# 6N137.net
KiCad netlist of a schematic drawn in EAGLE
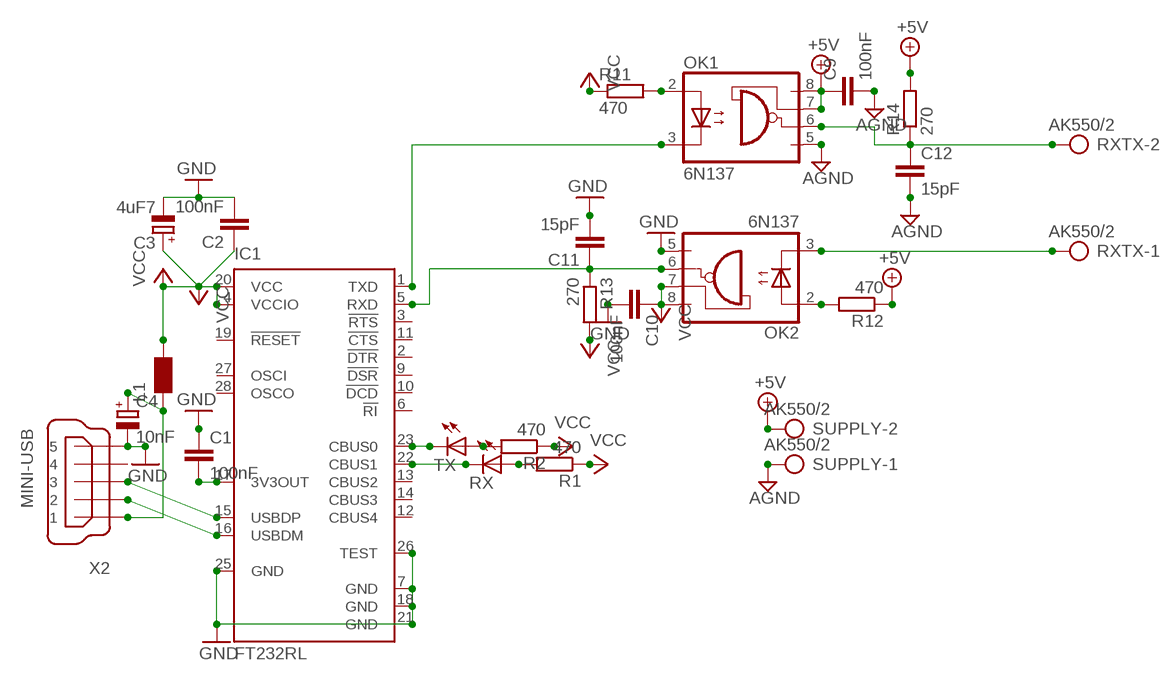
[diagram p0: schematic, sheet 1]

(export (version "E")
  (design (tool "Eeschema 10.0.6"))
  (components
    (comp (ref "C1")
      (value "100nF")
      (footprint "eagle-import:C1206K")
      (libsource (lib "eagle-import") (part "C-EUC1206K"))
    )
    (comp (ref "C2")
      (value "100nF")
      (footprint "eagle-import:C1206K")
      (libsource (lib "eagle-import") (part "C-EUC1206K"))
    )
    (comp (ref "C3")
      (value "4uF7")
      (footprint "eagle-import:153CLV-0605")
      (libsource (lib "eagle-import") (part "CPOL-EU153CLV-0605"))
    )
    (comp (ref "C4")
      (value "10nF")
      (footprint "eagle-import:153CLV-0405")
      (libsource (lib "eagle-import") (part "CPOL-EU153CLV-0405"))
    )
    (comp (ref "C9")
      (value "100nF")
      (footprint "eagle-import:C1206")
      (libsource (lib "eagle-import") (part "C-EUC1206"))
    )
    (comp (ref "C10")
      (value "100nF")
      (footprint "eagle-import:C1206")
      (libsource (lib "eagle-import") (part "C-EUC1206"))
    )
    (comp (ref "C11")
      (value "15pF")
      (footprint "eagle-import:C1206")
      (libsource (lib "eagle-import") (part "C-EUC1206"))
    )
    (comp (ref "C12")
      (value "15pF")
      (footprint "eagle-import:C1206")
      (libsource (lib "eagle-import") (part "C-EUC1206"))
    )
    (comp (ref "IC1")
      (value "FT232RL")
      (footprint "eagle-import:SSOP28")
      (libsource (lib "eagle-import") (part "FT232RL"))
    )
    (comp (ref "L1")
      (value "WE-CBF_1206")
      (footprint "eagle-import:1206")
      (libsource (lib "eagle-import") (part "WE-CBF_1206"))
    )
    (comp (ref "OK1")
      (value "6N137")
      (footprint "eagle-import:DIL08")
      (libsource (lib "eagle-import") (part "6N137"))
    )
    (comp (ref "OK2")
      (value "6N137")
      (footprint "eagle-import:DIL08")
      (libsource (lib "eagle-import") (part "6N137"))
    )
    (comp (ref "R1")
      (value "470")
      (footprint "eagle-import:M1206")
      (libsource (lib "eagle-import") (part "resistor_R-EU_M1206"))
    )
    (comp (ref "R2")
      (value "470")
      (footprint "eagle-import:M1206")
      (libsource (lib "eagle-import") (part "resistor_R-EU_M1206"))
    )
    (comp (ref "R11")
      (value "470")
      (footprint "eagle-import:R1206")
      (libsource (lib "eagle-import") (part "R-EU_R1206"))
    )
    (comp (ref "R12")
      (value "470")
      (footprint "eagle-import:R1206")
      (libsource (lib "eagle-import") (part "R-EU_R1206"))
    )
    (comp (ref "R13")
      (value "270")
      (footprint "eagle-import:R1206")
      (libsource (lib "eagle-import") (part "R-EU_R1206"))
    )
    (comp (ref "R14")
      (value "270")
      (footprint "eagle-import:R1206")
      (libsource (lib "eagle-import") (part "R-EU_R1206"))
    )
    (comp (ref "RX")
      (value "LEDCHIPLED_1206")
      (footprint "eagle-import:CHIPLED_1206")
      (libsource (lib "eagle-import") (part "LEDCHIPLED_1206"))
    )
    (comp (ref "RXTX")
      (value "AK550/2")
      (footprint "eagle-import:AK550_2")
      (libsource (lib "eagle-import") (part "AK550/2"))
    )
    (comp (ref "SUPPLY")
      (value "AK550/2")
      (footprint "eagle-import:AK550_2")
      (libsource (lib "eagle-import") (part "AK550/2"))
    )
    (comp (ref "TX")
      (value "LEDCHIPLED_1206")
      (footprint "eagle-import:CHIPLED_1206")
      (libsource (lib "eagle-import") (part "LEDCHIPLED_1206"))
    )
    (comp (ref "X2")
      (value "MINI-USB")
      (footprint "eagle-import:UX60A-MB-5ST")
      (libsource (lib "eagle-import") (part "MINI-USB-SHIELD-UX60A-MB-5ST"))
    )
  )
  (nets
    (net (code "1") (name "+5V") (class "Default")
      (node (ref "C9") (pin "1") (pinfunction "1_1") (pintype "passive"))
      (node (ref "OK1") (pin "7") (pinfunction "VE_7") (pintype "passive"))
      (node (ref "OK1") (pin "8") (pinfunction "VCC_8") (pintype "passive"))
      (node (ref "R12") (pin "1") (pinfunction "1_1") (pintype "passive"))
      (node (ref "R14") (pin "2") (pinfunction "2_2") (pintype "passive"))
      (node (ref "SUPPLY") (pin "2") (pinfunction "KL_2") (pintype "passive"))
    )
    (net (code "2") (name "AGND") (class "Default")
      (node (ref "C12") (pin "2") (pinfunction "2_2") (pintype "passive"))
      (node (ref "C9") (pin "2") (pinfunction "2_2") (pintype "passive"))
      (node (ref "OK1") (pin "5") (pinfunction "GND_5") (pintype "passive"))
      (node (ref "SUPPLY") (pin "1") (pinfunction "KL_1") (pintype "passive"))
    )
    (net (code "3") (name "GND") (class "Default")
      (node (ref "C1") (pin "1") (pinfunction "1_1") (pintype "passive"))
      (node (ref "C10") (pin "2") (pinfunction "2_2") (pintype "passive"))
      (node (ref "C11") (pin "2") (pinfunction "2_2") (pintype "passive"))
      (node (ref "C2") (pin "2") (pinfunction "2_2") (pintype "passive"))
      (node (ref "C3") (pin "-") (pinfunction "-_-") (pintype "passive"))
      (node (ref "C4") (pin "-") (pinfunction "-_-") (pintype "passive"))
      (node (ref "IC1") (pin "18") (pinfunction "GND_18") (pintype "input"))
      (node (ref "IC1") (pin "21") (pinfunction "GND_21") (pintype "input"))
      (node (ref "IC1") (pin "25") (pinfunction "GND_25") (pintype "input"))
      (node (ref "IC1") (pin "26") (pinfunction "TEST_26") (pintype "input"))
      (node (ref "IC1") (pin "7") (pinfunction "GND_7") (pintype "input"))
      (node (ref "OK2") (pin "5") (pinfunction "GND_5") (pintype "passive"))
      (node (ref "X2") (pin "5") (pinfunction "5_5") (pintype "input"))
    )
    (net (code "4") (name "Net-(C4-Pad+)") (class "Default")
      (node (ref "C4") (pin "+") (pinfunction "+_+") (pintype "passive"))
      (node (ref "L1") (pin "1") (pinfunction "1_1") (pintype "passive"))
      (node (ref "X2") (pin "1") (pinfunction "1_1") (pintype "input"))
    )
    (net (code "5") (name "Net-(IC1-3V3OUT)") (class "Default")
      (node (ref "C1") (pin "2") (pinfunction "2_2") (pintype "passive"))
      (node (ref "IC1") (pin "17") (pinfunction "3V3OUT_17") (pintype "input"))
    )
    (net (code "6") (name "Net-(IC1-CBUS0)") (class "Default")
      (node (ref "IC1") (pin "23") (pinfunction "CBUS0_23") (pintype "input"))
      (node (ref "TX") (pin "C") (pinfunction "C_C") (pintype "passive"))
    )
    (net (code "7") (name "Net-(IC1-CBUS1)") (class "Default")
      (node (ref "IC1") (pin "22") (pinfunction "CBUS1_22") (pintype "input"))
      (node (ref "RX") (pin "C") (pinfunction "C_C") (pintype "passive"))
    )
    (net (code "8") (name "Net-(IC1-RXD)") (class "Default")
      (node (ref "C11") (pin "1") (pinfunction "1_1") (pintype "passive"))
      (node (ref "IC1") (pin "5") (pinfunction "RXD_5") (pintype "input"))
      (node (ref "OK2") (pin "6") (pinfunction "VO_6") (pintype "passive"))
      (node (ref "R13") (pin "1") (pinfunction "1_1") (pintype "passive"))
    )
    (net (code "9") (name "Net-(IC1-TXD)") (class "Default")
      (node (ref "IC1") (pin "1") (pinfunction "TXD_1") (pintype "input"))
      (node (ref "OK1") (pin "3") (pinfunction "C_3") (pintype "passive"))
    )
    (net (code "10") (name "Net-(IC1-USBDM)") (class "Default")
      (node (ref "IC1") (pin "16") (pinfunction "USBDM_16") (pintype "input"))
      (node (ref "X2") (pin "2") (pinfunction "2_2") (pintype "input"))
    )
    (net (code "11") (name "Net-(IC1-USBDP)") (class "Default")
      (node (ref "IC1") (pin "15") (pinfunction "USBDP_15") (pintype "input"))
      (node (ref "X2") (pin "3") (pinfunction "3_3") (pintype "input"))
    )
    (net (code "12") (name "Net-(OK1-A)") (class "Default")
      (node (ref "OK1") (pin "2") (pinfunction "A_2") (pintype "passive"))
      (node (ref "R11") (pin "2") (pinfunction "2_2") (pintype "passive"))
    )
    (net (code "13") (name "Net-(OK1-VO)") (class "Default")
      (node (ref "C12") (pin "1") (pinfunction "1_1") (pintype "passive"))
      (node (ref "OK1") (pin "6") (pinfunction "VO_6") (pintype "passive"))
      (node (ref "R14") (pin "1") (pinfunction "1_1") (pintype "passive"))
      (node (ref "RXTX") (pin "2") (pinfunction "KL_2") (pintype "passive"))
    )
    (net (code "14") (name "Net-(OK2-A)") (class "Default")
      (node (ref "OK2") (pin "2") (pinfunction "A_2") (pintype "passive"))
      (node (ref "R12") (pin "2") (pinfunction "2_2") (pintype "passive"))
    )
    (net (code "15") (name "Net-(OK2-C)") (class "Default")
      (node (ref "OK2") (pin "3") (pinfunction "C_3") (pintype "passive"))
      (node (ref "RXTX") (pin "1") (pinfunction "KL_1") (pintype "passive"))
    )
    (net (code "16") (name "Net-(R1-Pad2)") (class "Default")
      (node (ref "R1") (pin "2") (pinfunction "2_2") (pintype "passive"))
      (node (ref "RX") (pin "A") (pinfunction "A_A") (pintype "passive"))
    )
    (net (code "17") (name "Net-(R2-Pad2)") (class "Default")
      (node (ref "R2") (pin "2") (pinfunction "2_2") (pintype "passive"))
      (node (ref "TX") (pin "A") (pinfunction "A_A") (pintype "passive"))
    )
    (net (code "18") (name "VCC") (class "Default")
      (node (ref "C10") (pin "1") (pinfunction "1_1") (pintype "passive"))
      (node (ref "C2") (pin "1") (pinfunction "1_1") (pintype "passive"))
      (node (ref "C3") (pin "+") (pinfunction "+_+") (pintype "passive"))
      (node (ref "IC1") (pin "20") (pinfunction "VCC_20") (pintype "input"))
      (node (ref "IC1") (pin "4") (pinfunction "VCCIO_4") (pintype "input"))
      (node (ref "L1") (pin "2") (pinfunction "2_2") (pintype "passive"))
      (node (ref "OK2") (pin "7") (pinfunction "VE_7") (pintype "passive"))
      (node (ref "OK2") (pin "8") (pinfunction "VCC_8") (pintype "passive"))
      (node (ref "R1") (pin "1") (pinfunction "1_1") (pintype "passive"))
      (node (ref "R11") (pin "1") (pinfunction "1_1") (pintype "passive"))
      (node (ref "R13") (pin "2") (pinfunction "2_2") (pintype "passive"))
      (node (ref "R2") (pin "1") (pinfunction "1_1") (pintype "passive"))
    )
    (net (code "19") (name "unconnected-(IC1-CBUS2-Pad13)") (class "Default")
      (node (ref "IC1") (pin "13") (pinfunction "CBUS2_13") (pintype "input"))
    )
    (net (code "20") (name "unconnected-(IC1-CBUS3-Pad14)") (class "Default")
      (node (ref "IC1") (pin "14") (pinfunction "CBUS3_14") (pintype "input"))
    )
    (net (code "21") (name "unconnected-(IC1-CBUS4-Pad12)") (class "Default")
      (node (ref "IC1") (pin "12") (pinfunction "CBUS4_12") (pintype "input"))
    )
    (net (code "22") (name "unconnected-(IC1-OSCI-Pad27)") (class "Default")
      (node (ref "IC1") (pin "27") (pinfunction "OSCI_27") (pintype "input"))
    )
    (net (code "23") (name "unconnected-(IC1-OSCO-Pad28)") (class "Default")
      (node (ref "IC1") (pin "28") (pinfunction "OSCO_28") (pintype "input"))
    )
    (net (code "24") (name "unconnected-(IC1-~{CTS}-Pad11)") (class "Default")
      (node (ref "IC1") (pin "11") (pinfunction "~{CTS}_11") (pintype "input"))
    )
    (net (code "25") (name "unconnected-(IC1-~{DCD}-Pad10)") (class "Default")
      (node (ref "IC1") (pin "10") (pinfunction "~{DCD}_10") (pintype "input"))
    )
    (net (code "26") (name "unconnected-(IC1-~{DSR}-Pad9)") (class "Default")
      (node (ref "IC1") (pin "9") (pinfunction "~{DSR}_9") (pintype "input"))
    )
    (net (code "27") (name "unconnected-(IC1-~{DTR}-Pad2)") (class "Default")
      (node (ref "IC1") (pin "2") (pinfunction "~{DTR}_2") (pintype "input"))
    )
    (net (code "28") (name "unconnected-(IC1-~{RESET}-Pad19)") (class "Default")
      (node (ref "IC1") (pin "19") (pinfunction "~{RESET}_19") (pintype "input"))
    )
    (net (code "29") (name "unconnected-(IC1-~{RI}-Pad6)") (class "Default")
      (node (ref "IC1") (pin "6") (pinfunction "~{RI}_6") (pintype "input"))
    )
    (net (code "30") (name "unconnected-(IC1-~{RTS}-Pad3)") (class "Default")
      (node (ref "IC1") (pin "3") (pinfunction "~{RTS}_3") (pintype "input"))
    )
    (net (code "31") (name "unconnected-(X2-Pad4)") (class "Default")
      (node (ref "X2") (pin "4") (pinfunction "4_4") (pintype "input"))
    )
  )
)
